# Attiny_sender.net
KiCad netlist of a schematic drawn in EasyEDA
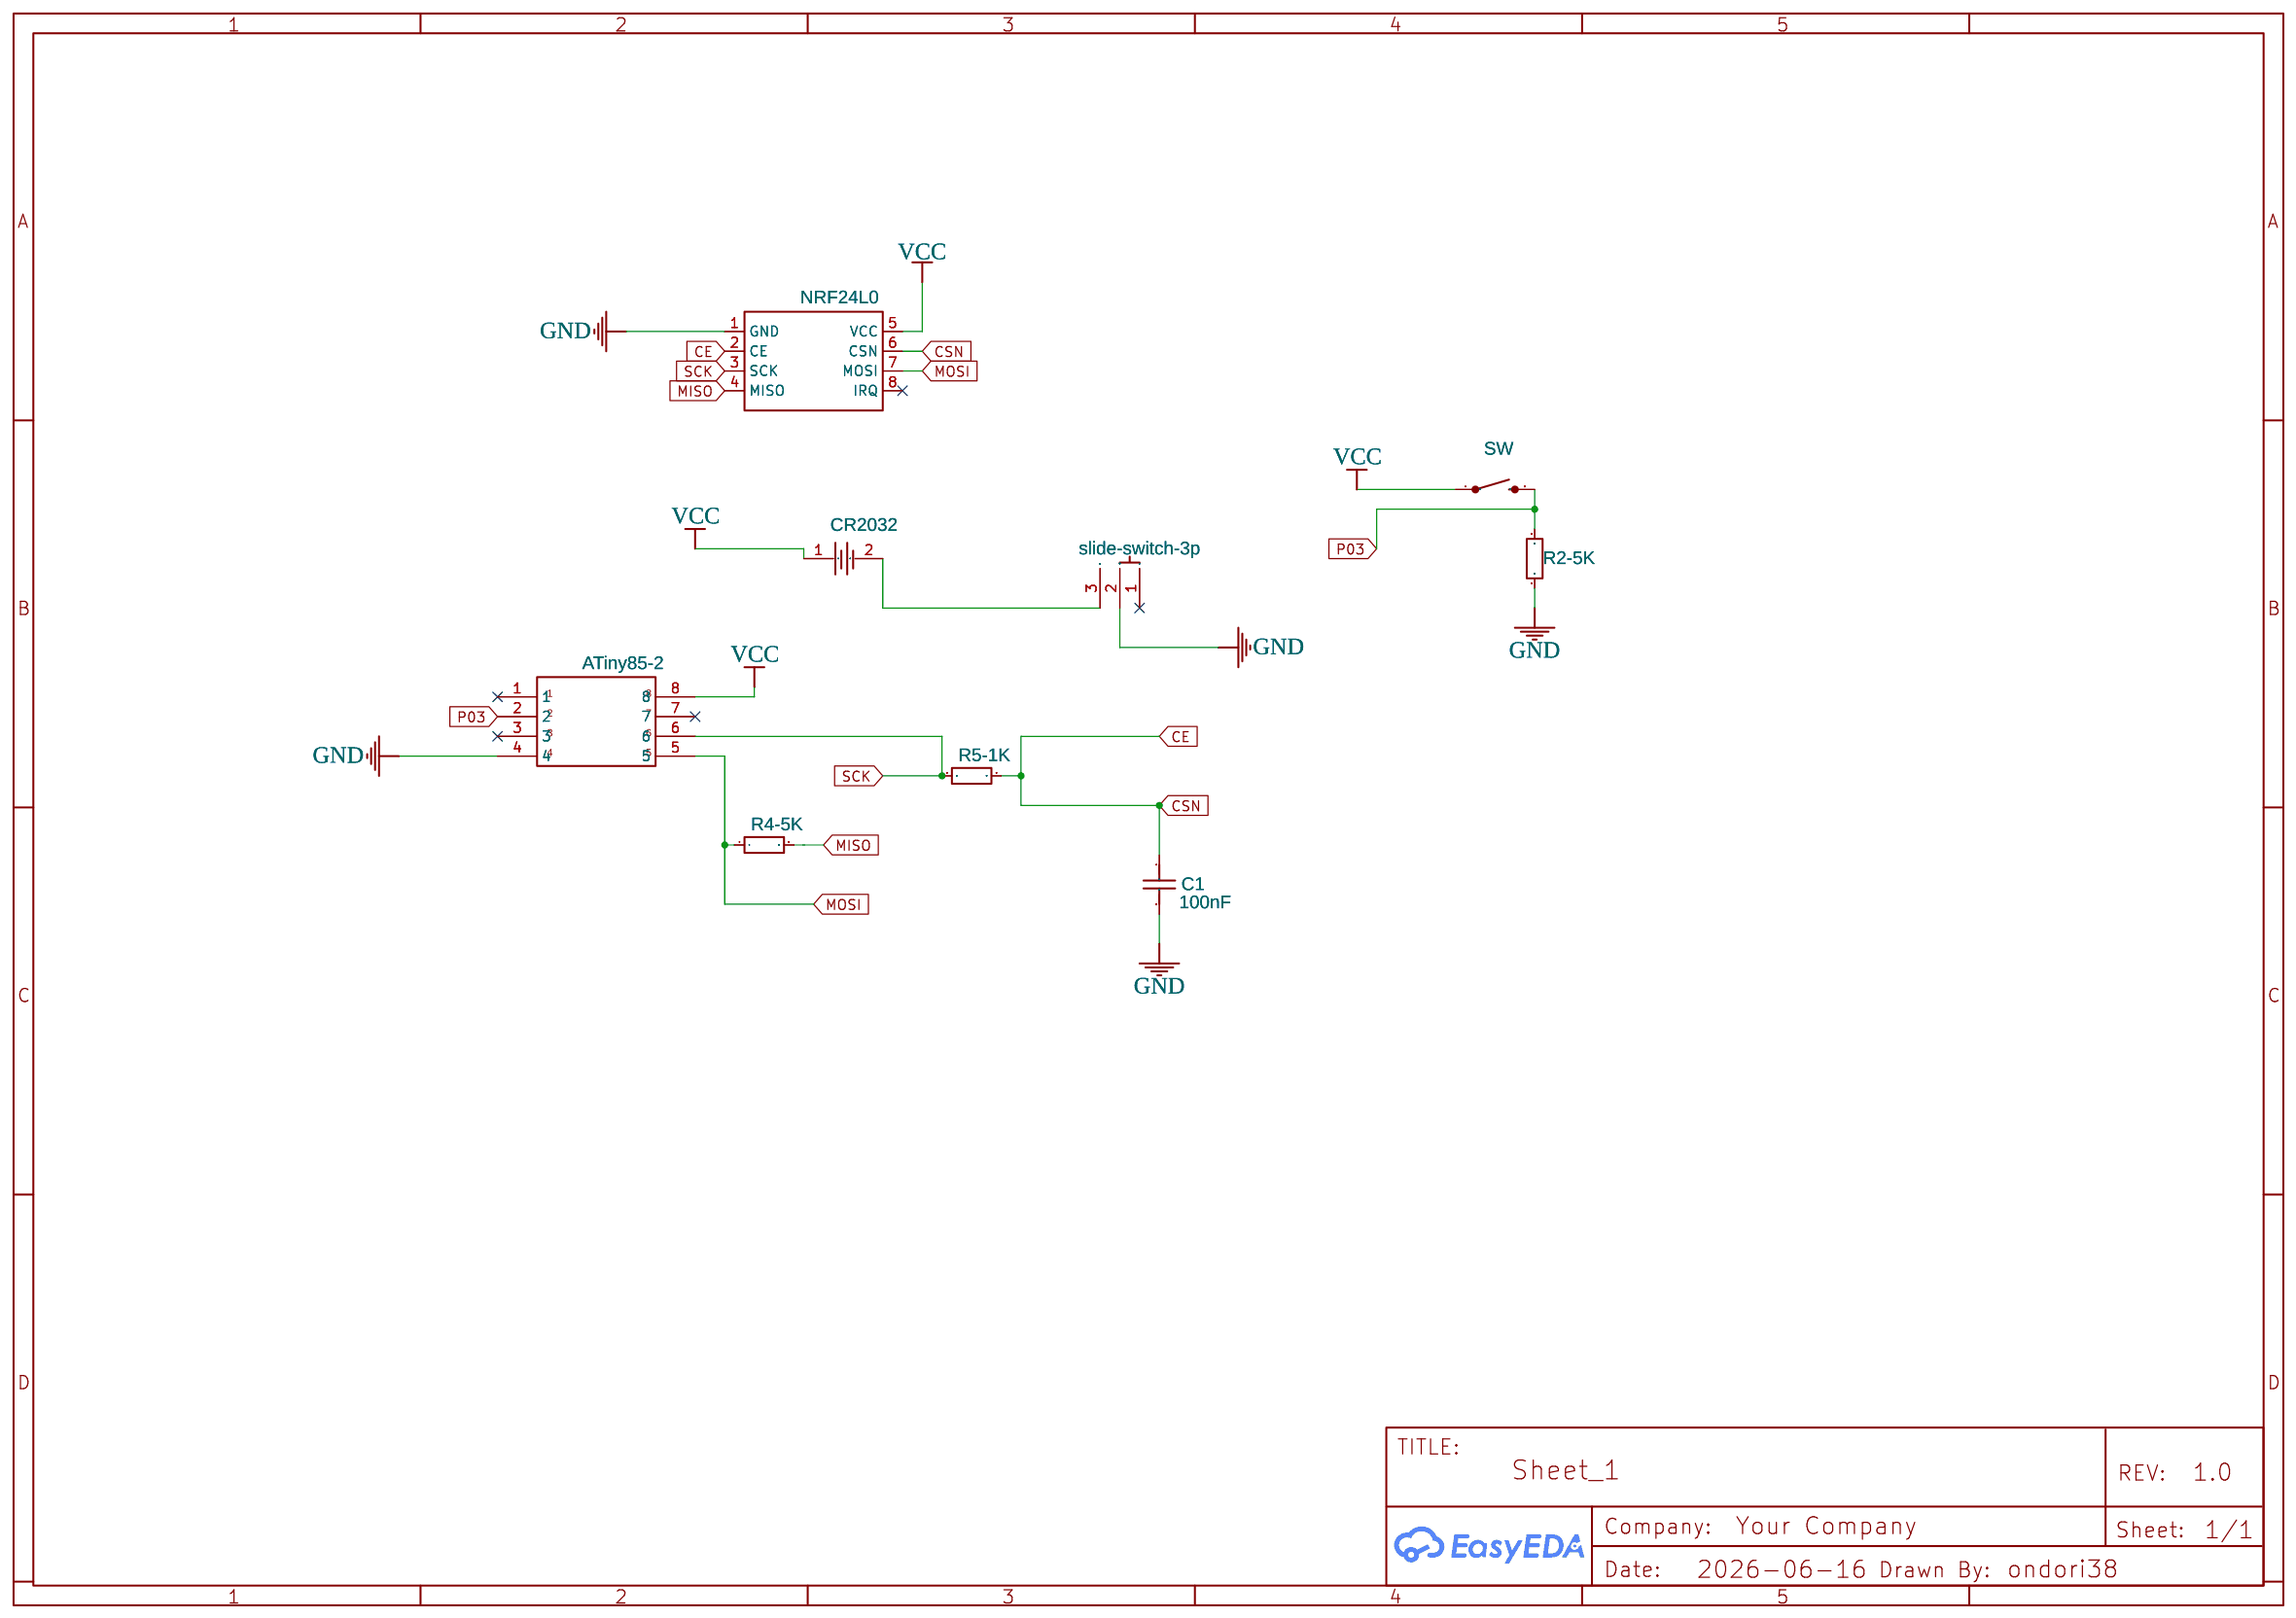
[diagram p0: schematic sheet]

(export (version "E")
  (design (tool "Eeschema 10.0.6"))
  (components
    (comp (ref "A1") (value "NRF24L0") (libsource (lib "") (part "NEF24L0")))
    (comp (ref "B1") (value "CR2032") (libsource (lib "") (part "BATT-CR2032")))
    (comp (ref "C1")
      (value "100nF")
      (fields (field (name "Manufacturer Part") "Capacitor-1206"))
      (libsource (lib "") (part "Capacitor SMD 1206"))
    )
    (comp (ref "R2")
      (value "R2-5K")
      (fields (field (name "Manufacturer Part") "C136529"))
      (libsource (lib "") (part "Resistor_THT_12,7mm_1"))
    )
    (comp (ref "R4")
      (value "R4-5K")
      (fields (field (name "Manufacturer Part") "C136529"))
      (libsource (lib "") (part "Resistor_THT_12,7mm"))
    )
    (comp (ref "R5")
      (value "R5-1K")
      (fields (field (name "Manufacturer Part") "C136529"))
      (libsource (lib "") (part "Resistor_THT_12,7mm"))
    )
    (comp (ref "SW") (value "SWITCHES_PTH_EZ") (libsource (lib "") (part "SWITCHES_PTH_EZ")))
    (comp (ref "SW2")
      (value "slide-switch-3p")
      (libsource (lib "") (part "slide-switch-3p-p3mm-handle-height"))
    )
    (comp (ref "U1") (value "ATiny85-2") (libsource (lib "") (part "ATiny85-2")))
  )
  (nets
    (net (code "1") (name "CE") (class "Default")
      (node (ref "A1") (pin "2") (pinfunction "CE_2") (pintype "unspecified"))
      (node (ref "A1") (pin "6") (pinfunction "CSN_6") (pintype "unspecified"))
      (node (ref "C1") (pin "1") (pinfunction "1_1") (pintype "unspecified"))
      (node (ref "R5") (pin "2") (pinfunction "2_2") (pintype "unspecified"))
    )
    (net (code "2") (name "GND") (class "Default")
      (node (ref "A1") (pin "1") (pinfunction "GND_1") (pintype "unspecified"))
      (node (ref "C1") (pin "2") (pinfunction "2_2") (pintype "unspecified"))
      (node (ref "R2") (pin "1") (pinfunction "1_1") (pintype "unspecified"))
      (node (ref "SW2") (pin "2") (pinfunction "COM_2") (pintype "unspecified"))
      (node (ref "U1") (pin "4") (pinfunction "4_4") (pintype "unspecified"))
    )
    (net (code "3") (name "MISO") (class "Default")
      (node (ref "A1") (pin "4") (pinfunction "MISO_4") (pintype "unspecified"))
      (node (ref "R4") (pin "2") (pinfunction "2_2") (pintype "unspecified"))
    )
    (net (code "4") (name "MOSI") (class "Default")
      (node (ref "A1") (pin "7") (pinfunction "MOSI_7") (pintype "unspecified"))
      (node (ref "R4") (pin "1") (pinfunction "1_1") (pintype "unspecified"))
      (node (ref "U1") (pin "5") (pinfunction "5_5") (pintype "unspecified"))
    )
    (net (code "5") (name "Net-(B1-Pad2)") (class "Default")
      (node (ref "B1") (pin "2") (pinfunction "2_2") (pintype "input"))
      (node (ref "SW2") (pin "3") (pinfunction "3_3") (pintype "unspecified"))
    )
    (net (code "6") (name "P03") (class "Default")
      (node (ref "R2") (pin "2") (pinfunction "2_2") (pintype "unspecified"))
      (node (ref "SW") (pin "3") (pinfunction "2_3") (pintype "unspecified"))
      (node (ref "U1") (pin "2") (pinfunction "2_2") (pintype "unspecified"))
    )
    (net (code "7") (name "SCK") (class "Default")
      (node (ref "A1") (pin "3") (pinfunction "SCK_3") (pintype "unspecified"))
      (node (ref "R5") (pin "1") (pinfunction "1_1") (pintype "unspecified"))
      (node (ref "U1") (pin "6") (pinfunction "6_6") (pintype "unspecified"))
    )
    (net (code "8") (name "VCC") (class "Default")
      (node (ref "A1") (pin "5") (pinfunction "VCC_5") (pintype "unspecified"))
      (node (ref "B1") (pin "1") (pinfunction "1_1") (pintype "input"))
      (node (ref "SW") (pin "1") (pinfunction "1_1") (pintype "unspecified"))
      (node (ref "U1") (pin "8") (pinfunction "8_8") (pintype "unspecified"))
    )
    (net (code "9") (name "unconnected-(A1-IRQ-Pad8)") (class "Default")
      (node (ref "A1") (pin "8") (pinfunction "IRQ_8") (pintype "unspecified+no_connect"))
    )
    (net (code "10") (name "unconnected-(SW2-Pad1)") (class "Default")
      (node (ref "SW2") (pin "1") (pinfunction "1_1") (pintype "unspecified+no_connect"))
    )
    (net (code "11") (name "unconnected-(U1-Pad1)") (class "Default")
      (node (ref "U1") (pin "1") (pinfunction "1_1") (pintype "unspecified+no_connect"))
    )
    (net (code "12") (name "unconnected-(U1-Pad3)") (class "Default")
      (node (ref "U1") (pin "3") (pinfunction "3_3") (pintype "unspecified+no_connect"))
    )
    (net (code "13") (name "unconnected-(U1-Pad7)") (class "Default")
      (node (ref "U1") (pin "7") (pinfunction "7_7") (pintype "unspecified+no_connect"))
    )
  )
)
